# Step-up_DC-DC_Converter.net
KiCad netlist of a schematic drawn in Altium Designer
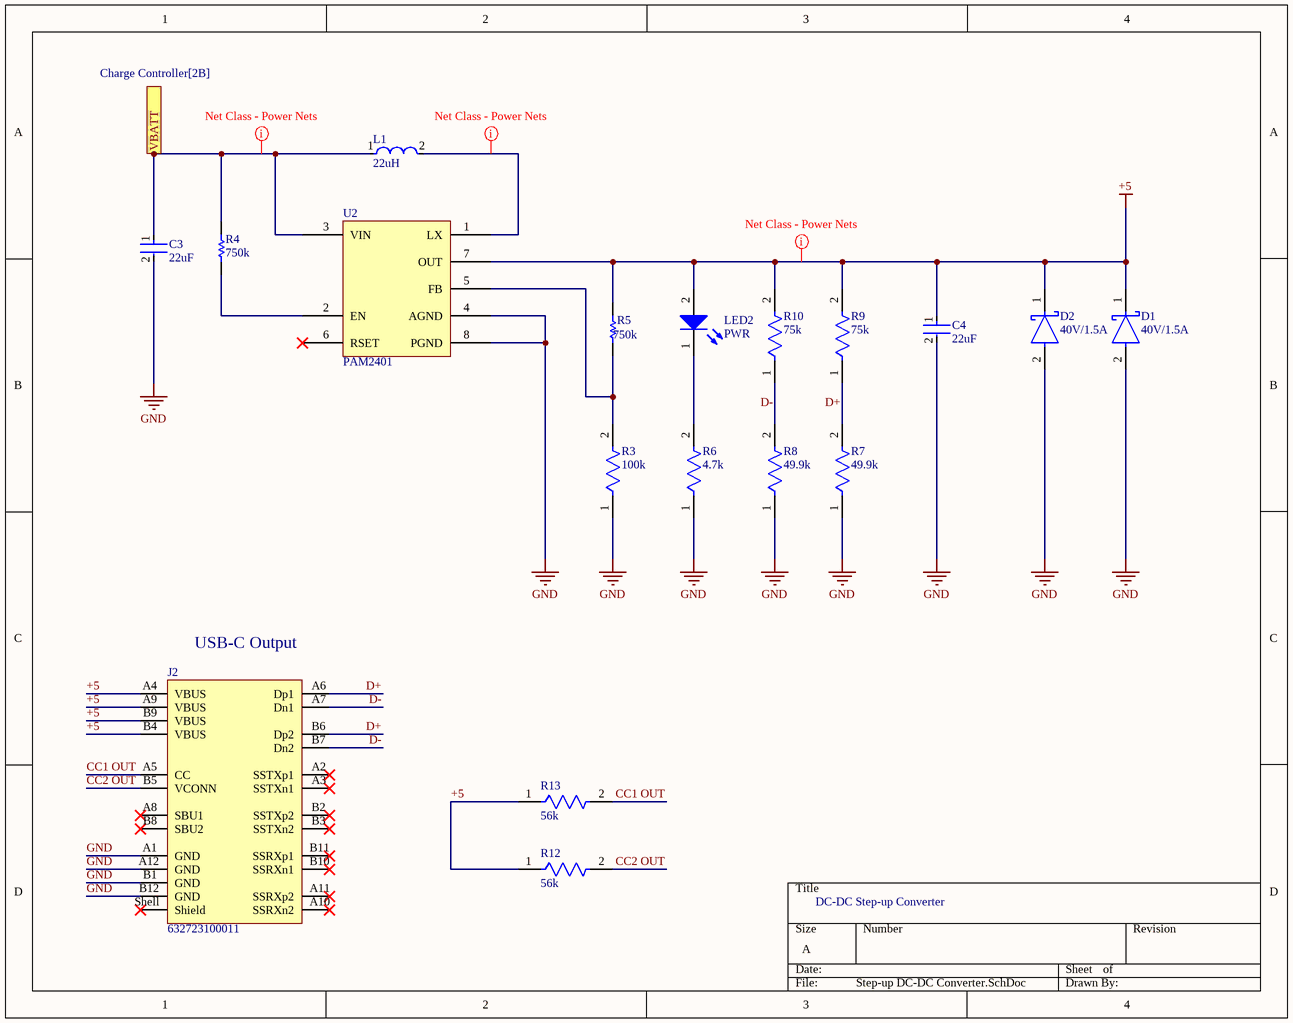
[diagram p0: Step-up DC-DC Converter.SchDoc]

(export (version "E")
  (design (tool "Eeschema 10.0.6"))
  (components
    (comp (ref "C3")
      (value "22uF")
      (footprint "FP-GRM21B-0_15-MFG")
      (description "Chip Multilayer Ceramic Capacitors for General Purpose, 0805, 22uF, X5R, 15%, 20%, 6.3V")
      (fields (field (name "VOLTAGE") "6.3V") (field (name "TOLERANCE") "20%"))
      (libsource (lib "Altium Content Vault") (part "b4654b650e69147ec39a6b967a45e02"))
    )
    (comp (ref "C4")
      (value "22uF")
      (footprint "FP-GRM21B-0_15-MFG")
      (description "Chip Multilayer Ceramic Capacitors for General Purpose, 0805, 22uF, X5R, 15%, 20%, 6.3V")
      (fields (field (name "VOLTAGE") "6.3V") (field (name "TOLERANCE") "20%"))
      (libsource (lib "Altium Content Vault") (part "b4654b650e69147ec39a6b967a45e02"))
    )
    (comp (ref "D1")
      (value "40V/1.5A")
      (footprint "FP-95400-MFG")
      (description "DIODE SCHOTTKY 40V 1.5A SMA")
      (fields
        (field (name "OCTOPART") "https://octopart.com/vs-15mq040ntrpbf-vishay-44340959")
        (field (name "MANUFACTURER") "Vishay")
      )
      (libsource (lib "Altium Content Vault") (part "c1678fac7984e62e0809fbf79c06691"))
    )
    (comp (ref "D2")
      (value "40V/1.5A")
      (footprint "FP-95400-MFG")
      (description "DIODE SCHOTTKY 40V 1.5A SMA")
      (fields
        (field (name "OCTOPART") "https://octopart.com/vs-15mq040ntrpbf-vishay-44340959")
        (field (name "MANUFACTURER") "Vishay")
      )
      (libsource (lib "Altium Content Vault") (part "c1678fac7984e62e0809fbf79c06691"))
    )
    (comp (ref "J2")
      (value "632723100011")
      (footprint "632723100011")
      (libsource (lib "Altium Content Vault") (part "USB 3.1_Type C_Receptacle_1 Port"))
    )
    (comp (ref "L1")
      (value "22uH")
      (footprint "FP-LQM2HPN_G0-IPC_C")
      (description "Multilayer Type Inductor for Power Lines, 1008 (2520), 2.2μH, 20%, 0.225Ω, 1100mA")
      (fields (field (name "TOLERANCE") "20%"))
      (libsource (lib "Altium Content Vault") (part "725321dda6339637d4d059423bc1c3c"))
    )
    (comp (ref "LED2")
      (value "PWR")
      (footprint "WL-SMCW_0805_150080xx75000")
      (description "Led, Blue, 470 Nm, 3.2 V, 30 Ma, 145 Mcd Rohs Compliant: Yes")
      (libsource (lib "Altium Content Vault") (part "LED_Blue_2A-1K"))
    )
    (comp (ref "R3")
      (value "100k")
      (footprint "FP-CRCW0805-e3-MFG")
      (description "RES Thick Film, 100kΩ, 1%, 0.125W, 100ppm/°C, 0805")
      (fields (field (name "TOLERANCE") "1%"))
      (libsource (lib "Altium Content Vault") (part "1029c3af85768c4190bb7ad29bc67b5"))
    )
    (comp (ref "R4")
      (value "750k")
      (footprint "RESC2013X50X30LL20T20")
      (fields (field (name "MANUFACTURER") "Vishay Dale") (field (name "PART NUMBER") "CRCW0805750KFKEA"))
      (libsource (lib "Altium Content Vault") (part "RES"))
    )
    (comp (ref "R5")
      (value "750k")
      (footprint "RESC2013X50X30LL20T20")
      (fields (field (name "MANUFACTURER") "Vishay Dale") (field (name "PART NUMBER") "CRCW0805750KFKEA"))
      (libsource (lib "Altium Content Vault") (part "RES"))
    )
    (comp (ref "R6")
      (value "4.7k")
      (footprint "FP-CRCW0805-e3-IPC_B")
      (description "RES Thick Film, 4.7kΩ, 1%, 0.125W, 100ppm/°C, 0805")
      (fields (field (name "TOLERANCE") "1%"))
      (libsource (lib "Altium Content Vault") (part "1029c3af85768c4190bb7ad29bc67b5"))
    )
    (comp (ref "R7")
      (value "49.9k")
      (footprint "FP-CRCW0805-e3-IPC_C")
      (description "RES Thick Film, 49.9kΩ, 1%, 0.125W, 100ppm/°C, 0805")
      (fields (field (name "TOLERANCE") "1%"))
      (libsource (lib "Altium Content Vault") (part "1029c3af85768c4190bb7ad29bc67b5"))
    )
    (comp (ref "R8")
      (value "49.9k")
      (footprint "FP-CRCW0805-e3-IPC_C")
      (description "RES Thick Film, 49.9kΩ, 1%, 0.125W, 100ppm/°C, 0805")
      (fields (field (name "TOLERANCE") "1%"))
      (libsource (lib "Altium Content Vault") (part "1029c3af85768c4190bb7ad29bc67b5"))
    )
    (comp (ref "R9")
      (value "75k")
      (footprint "FP-CRCW0805-e3-IPC_A")
      (description "RES Thick Film, 75kΩ, 1%, 0.125W, 100ppm/°C, 0805")
      (fields (field (name "TOLERANCE") "1%"))
      (libsource (lib "Altium Content Vault") (part "1029c3af85768c4190bb7ad29bc67b5"))
    )
    (comp (ref "R10")
      (value "75k")
      (footprint "FP-CRCW0805-e3-IPC_A")
      (description "RES Thick Film, 75kΩ, 1%, 0.125W, 100ppm/°C, 0805")
      (fields (field (name "TOLERANCE") "1%"))
      (libsource (lib "Altium Content Vault") (part "1029c3af85768c4190bb7ad29bc67b5"))
    )
    (comp (ref "R12")
      (value "56k")
      (footprint "FP-CRCW0805-e3-IPC_B")
      (description "RES Thick Film, 56kΩ, 1%, 0.125W, 100ppm/°C, 0805")
      (fields (field (name "TOLERANCE") "1%"))
      (libsource (lib "Altium Content Vault") (part "1029c3af85768c4190bb7ad29bc67b5"))
    )
    (comp (ref "R13")
      (value "56k")
      (footprint "FP-CRCW0805-e3-IPC_B")
      (description "RES Thick Film, 56kΩ, 1%, 0.125W, 100ppm/°C, 0805")
      (fields (field (name "TOLERANCE") "1%"))
      (libsource (lib "Altium Content Vault") (part "1029c3af85768c4190bb7ad29bc67b5"))
    )
    (comp (ref "U2")
      (value "PAM2401")
      (footprint "TSOP65P490X110-8N")
      (description "1.0MHz STEP-UP DC-DC CONVERTER")
      (libsource (lib "CustomLib") (part "PAM2401"))
    )
  )
  (nets
    (net (code "1") (name "+5") (class "Default")
      (node (ref "C4") (pin "1") (pinfunction "1_1") (pintype "passive"))
      (node (ref "D1") (pin "1") (pinfunction "C_1") (pintype "passive"))
      (node (ref "D2") (pin "1") (pinfunction "C_1") (pintype "passive"))
      (node (ref "J2") (pin "A4") (pinfunction "VBUS_A4") (pintype "passive"))
      (node (ref "J2") (pin "A9") (pinfunction "VBUS_A9") (pintype "passive"))
      (node (ref "J2") (pin "B4") (pinfunction "VBUS_B4") (pintype "passive"))
      (node (ref "J2") (pin "B9") (pinfunction "VBUS_B9") (pintype "passive"))
      (node (ref "LED2") (pin "2") (pinfunction "A_2") (pintype "passive"))
      (node (ref "R10") (pin "2") (pinfunction "2_2") (pintype "passive"))
      (node (ref "R12") (pin "1") (pinfunction "1_1") (pintype "passive"))
      (node (ref "R13") (pin "1") (pinfunction "1_1") (pintype "passive"))
      (node (ref "R5") (pin "2") (pinfunction "2_2") (pintype "passive"))
      (node (ref "R9") (pin "2") (pinfunction "2_2") (pintype "passive"))
      (node (ref "U2") (pin "7") (pinfunction "OUT_7") (pintype "passive"))
    )
    (net (code "2") (name "/CC1 OUT") (class "Default")
      (node (ref "J2") (pin "A5") (pinfunction "CC_A5") (pintype "passive"))
      (node (ref "R13") (pin "2") (pinfunction "2_2") (pintype "passive"))
    )
    (net (code "3") (name "/CC2 OUT") (class "Default")
      (node (ref "J2") (pin "B5") (pinfunction "VCONN_B5") (pintype "passive"))
      (node (ref "R12") (pin "2") (pinfunction "2_2") (pintype "passive"))
    )
    (net (code "4") (name "/D+") (class "Default")
      (node (ref "J2") (pin "A6") (pinfunction "Dp1_A6") (pintype "passive"))
      (node (ref "J2") (pin "B6") (pinfunction "Dp2_B6") (pintype "passive"))
      (node (ref "R7") (pin "2") (pinfunction "2_2") (pintype "passive"))
      (node (ref "R9") (pin "1") (pinfunction "1_1") (pintype "passive"))
    )
    (net (code "5") (name "/D-") (class "Default")
      (node (ref "J2") (pin "A7") (pinfunction "Dn1_A7") (pintype "passive"))
      (node (ref "J2") (pin "B7") (pinfunction "Dn2_B7") (pintype "passive"))
      (node (ref "R10") (pin "1") (pinfunction "1_1") (pintype "passive"))
      (node (ref "R8") (pin "2") (pinfunction "2_2") (pintype "passive"))
    )
    (net (code "6") (name "/VBATT") (class "Default")
      (node (ref "C3") (pin "1") (pinfunction "1_1") (pintype "passive"))
      (node (ref "L1") (pin "1") (pinfunction "1_1") (pintype "passive"))
      (node (ref "R4") (pin "2") (pinfunction "2_2") (pintype "passive"))
      (node (ref "U2") (pin "3") (pinfunction "VIN_3") (pintype "passive"))
    )
    (net (code "7") (name "GND") (class "Default")
      (node (ref "C3") (pin "2") (pinfunction "2_2") (pintype "passive"))
      (node (ref "C4") (pin "2") (pinfunction "2_2") (pintype "passive"))
      (node (ref "D1") (pin "2") (pinfunction "A_2") (pintype "passive"))
      (node (ref "D2") (pin "2") (pinfunction "A_2") (pintype "passive"))
      (node (ref "J2") (pin "A1") (pinfunction "GND_A1") (pintype "passive"))
      (node (ref "J2") (pin "A12") (pinfunction "GND_A12") (pintype "passive"))
      (node (ref "J2") (pin "B1") (pinfunction "GND_B1") (pintype "passive"))
      (node (ref "J2") (pin "B12") (pinfunction "GND_B12") (pintype "passive"))
      (node (ref "R3") (pin "1") (pinfunction "1_1") (pintype "passive"))
      (node (ref "R6") (pin "1") (pinfunction "1_1") (pintype "passive"))
      (node (ref "R7") (pin "1") (pinfunction "1_1") (pintype "passive"))
      (node (ref "R8") (pin "1") (pinfunction "1_1") (pintype "passive"))
      (node (ref "U2") (pin "4") (pinfunction "AGND_4") (pintype "passive"))
      (node (ref "U2") (pin "8") (pinfunction "PGND_8") (pintype "passive"))
    )
    (net (code "8") (name "Net-(LED2-K)") (class "Default")
      (node (ref "LED2") (pin "1") (pinfunction "K_1") (pintype "passive"))
      (node (ref "R6") (pin "2") (pinfunction "2_2") (pintype "passive"))
    )
    (net (code "9") (name "Net-(U2-EN)") (class "Default")
      (node (ref "R4") (pin "1") (pinfunction "1_1") (pintype "passive"))
      (node (ref "U2") (pin "2") (pinfunction "EN_2") (pintype "passive"))
    )
    (net (code "10") (name "Net-(U2-FB)") (class "Default")
      (node (ref "R3") (pin "2") (pinfunction "2_2") (pintype "passive"))
      (node (ref "R5") (pin "1") (pinfunction "1_1") (pintype "passive"))
      (node (ref "U2") (pin "5") (pinfunction "FB_5") (pintype "passive"))
    )
    (net (code "11") (name "Net-(U2-LX)") (class "Default")
      (node (ref "L1") (pin "2") (pinfunction "2_2") (pintype "passive"))
      (node (ref "U2") (pin "1") (pinfunction "LX_1") (pintype "passive"))
    )
    (net (code "12") (name "unconnected-(J2-SBU1-PadA8)") (class "Default")
      (node (ref "J2") (pin "A8") (pinfunction "SBU1_A8") (pintype "passive+no_connect"))
    )
    (net (code "13") (name "unconnected-(J2-SBU2-PadB8)") (class "Default")
      (node (ref "J2") (pin "B8") (pinfunction "SBU2_B8") (pintype "passive+no_connect"))
    )
    (net (code "14") (name "unconnected-(J2-SSRXn1-PadB10)") (class "Default")
      (node (ref "J2") (pin "B10") (pinfunction "SSRXn1_B10") (pintype "passive+no_connect"))
    )
    (net (code "15") (name "unconnected-(J2-SSRXn2-PadA10)") (class "Default")
      (node (ref "J2") (pin "A10") (pinfunction "SSRXn2_A10") (pintype "passive+no_connect"))
    )
    (net (code "16") (name "unconnected-(J2-SSRXp1-PadB11)") (class "Default")
      (node (ref "J2") (pin "B11") (pinfunction "SSRXp1_B11") (pintype "passive+no_connect"))
    )
    (net (code "17") (name "unconnected-(J2-SSRXp2-PadA11)") (class "Default")
      (node (ref "J2") (pin "A11") (pinfunction "SSRXp2_A11") (pintype "passive+no_connect"))
    )
    (net (code "18") (name "unconnected-(J2-SSTXn1-PadA3)") (class "Default")
      (node (ref "J2") (pin "A3") (pinfunction "SSTXn1_A3") (pintype "passive+no_connect"))
    )
    (net (code "19") (name "unconnected-(J2-SSTXn2-PadB3)") (class "Default")
      (node (ref "J2") (pin "B3") (pinfunction "SSTXn2_B3") (pintype "passive+no_connect"))
    )
    (net (code "20") (name "unconnected-(J2-SSTXp1-PadA2)") (class "Default")
      (node (ref "J2") (pin "A2") (pinfunction "SSTXp1_A2") (pintype "passive+no_connect"))
    )
    (net (code "21") (name "unconnected-(J2-SSTXp2-PadB2)") (class "Default")
      (node (ref "J2") (pin "B2") (pinfunction "SSTXp2_B2") (pintype "passive+no_connect"))
    )
    (net (code "22") (name "unconnected-(J2-Shield-PadShell)") (class "Default")
      (node (ref "J2") (pin "Shell") (pinfunction "Shield_Shell") (pintype "passive+no_connect"))
    )
    (net (code "23") (name "unconnected-(U2-RSET-Pad6)") (class "Default")
      (node (ref "U2") (pin "6") (pinfunction "RSET_6") (pintype "passive+no_connect"))
    )
  )
)
